# PushButtonside.net
KiCad netlist of a schematic drawn in Altium Designer
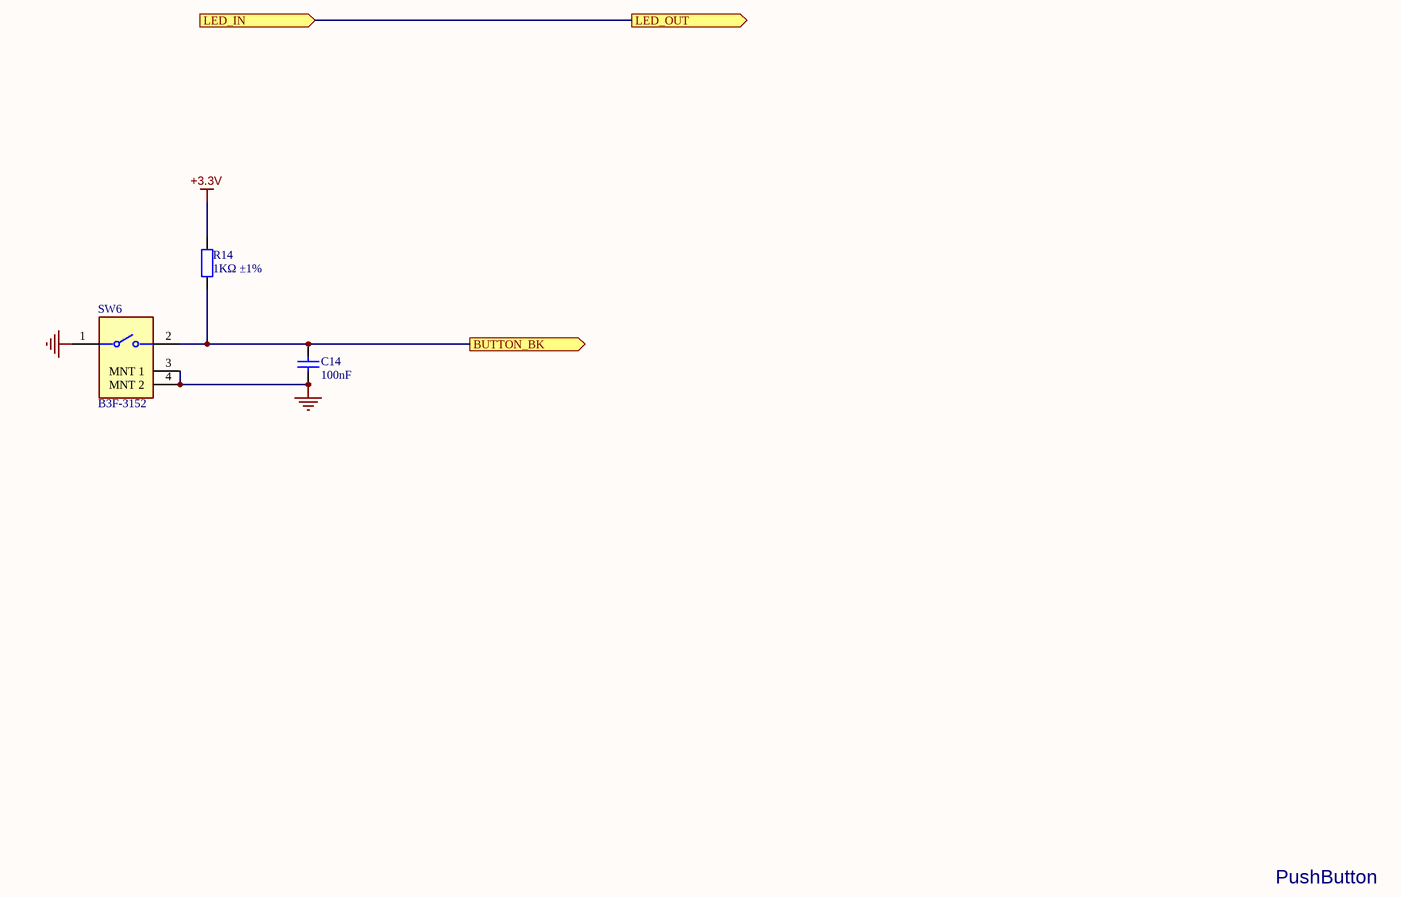
[diagram p0: PushButtonside.SchDoc]

(export (version "E")
  (design (tool "Eeschema 10.0.6"))
  (components
    (comp (ref "C14")
      (value "100nF")
      (footprint "0603_C")
      (description "Chip capacitors")
      (fields (field (name "MANUFACTURER") "YAGEO") (field (name "PARTNUMBER") "CC0603KRX7R9BB104"))
      (libsource (lib "Cap") (part "0603 100nF (104) 10% 50V"))
    )
    (comp (ref "R14")
      (value "1KΩ ±1%")
      (footprint "0603_R")
      (description "Chip resistor")
      (fields (field (name "MANUFACTURER") "Uniroyal Elec") (field (name "PARTNUMBER") "0603WAF1001T5E"))
      (libsource (lib "RES") (part "0603 1K (1001) 1%"))
    )
    (comp (ref "SW6")
      (value "B3F-3152")
      (footprint "FP-B3F-3152-MFG")
      (description "SWITCH TACTILE SPST-NO 0.05A 24V")
      (libsource (lib "Altium Content Vault") (part "ed2974a2078be5bbdf800c999931250"))
    )
  )
  (nets
    (net (code "1") (name "+3.3V") (class "Default")
      (node (ref "R14") (pin "1") (pinfunction "1_1") (pintype "passive"))
    )
    (net (code "2") (name "/BUTTON_BK") (class "Default")
      (node (ref "C14") (pin "1") (pinfunction "1_1") (pintype "passive"))
      (node (ref "R14") (pin "2") (pinfunction "2_2") (pintype "passive"))
      (node (ref "SW6") (pin "2") (pinfunction "2_2") (pintype "passive"))
    )
    (net (code "4") (name "GND") (class "Default")
      (node (ref "C14") (pin "2") (pinfunction "2_2") (pintype "passive"))
      (node (ref "SW6") (pin "1") (pinfunction "1_1") (pintype "passive"))
      (node (ref "SW6") (pin "3") (pinfunction "MNT_1_3") (pintype "passive"))
      (node (ref "SW6") (pin "4") (pinfunction "MNT_2_4") (pintype "passive"))
    )
  )
)
